# XenoGC.net
KiCad netlist of a schematic drawn in EAGLE
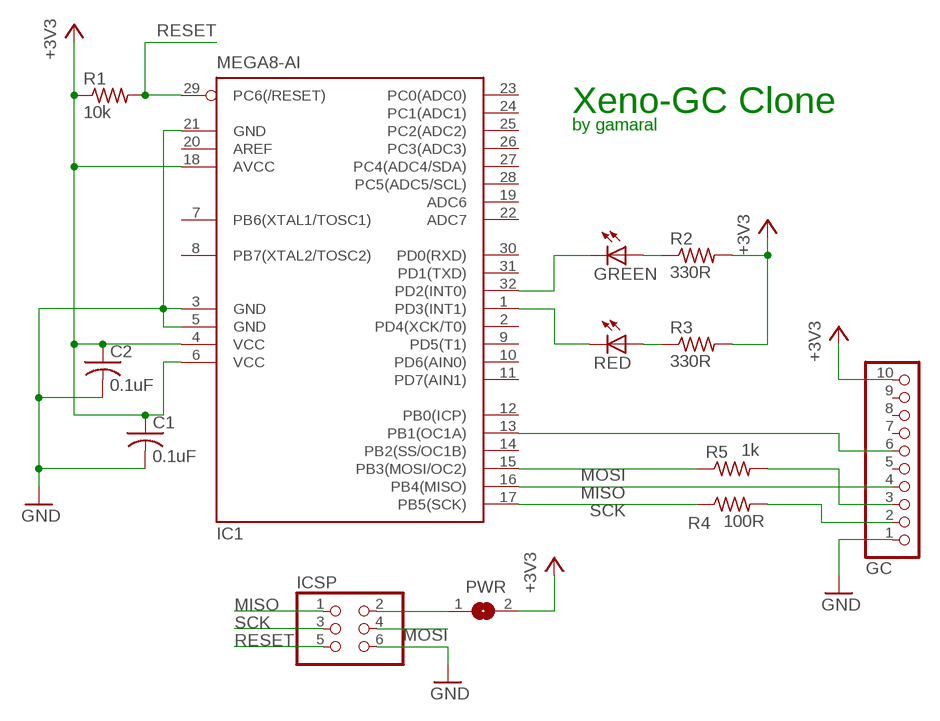
[diagram p0: schematic, sheet 1]

(export (version "E")
  (design (tool "Eeschema 10.0.6"))
  (components
    (comp (ref "C1")
      (value "0.1uF")
      (footprint "eagle-import:C0805K")
      (libsource (lib "eagle-import") (part "C-USC0805K"))
    )
    (comp (ref "C2")
      (value "0.1uF")
      (footprint "eagle-import:C0805K")
      (libsource (lib "eagle-import") (part "C-USC0805K"))
    )
    (comp (ref "GC")
      (value "PINHD-1X10")
      (footprint "eagle-import:1X10")
      (libsource (lib "eagle-import") (part "PINHD-1X10"))
    )
    (comp (ref "GREEN")
      (value "LEDSML1206")
      (footprint "eagle-import:SML1206")
      (libsource (lib "eagle-import") (part "LEDSML1206"))
    )
    (comp (ref "IC1")
      (value "MEGA8-AI")
      (footprint "eagle-import:TQFP32-08")
      (fields (field (name "MPN") "ATMEGA8-16AU"))
      (libsource (lib "eagle-import") (part "MEGA8-AI"))
    )
    (comp (ref "ICSP")
      (value "PINHD-2X3")
      (footprint "eagle-import:2X03")
      (libsource (lib "eagle-import") (part "PINHD-2X3"))
    )
    (comp (ref "PWR") (value "SJ") (footprint "eagle-import:SJ") (libsource (lib "eagle-import") (part "SJ")))
    (comp (ref "R1")
      (value "10k")
      (footprint "eagle-import:R0805W")
      (libsource (lib "eagle-import") (part "R-US_R0805W"))
    )
    (comp (ref "R2")
      (value "330R")
      (footprint "eagle-import:R0805W")
      (libsource (lib "eagle-import") (part "R-US_R0805W"))
    )
    (comp (ref "R3")
      (value "330R")
      (footprint "eagle-import:R0805W")
      (libsource (lib "eagle-import") (part "R-US_R0805W"))
    )
    (comp (ref "R4")
      (value "100R")
      (footprint "eagle-import:R0805W")
      (libsource (lib "eagle-import") (part "R-US_R0805W"))
    )
    (comp (ref "R5")
      (value "1k")
      (footprint "eagle-import:R0805W")
      (libsource (lib "eagle-import") (part "R-US_R0805W"))
    )
    (comp (ref "RED")
      (value "LEDSML1206")
      (footprint "eagle-import:SML1206")
      (libsource (lib "eagle-import") (part "LEDSML1206"))
    )
  )
  (nets
    (net (code "1") (name "+3V3") (class "Default")
      (node (ref "C1") (pin "1") (pinfunction "1_1") (pintype "passive"))
      (node (ref "C2") (pin "1") (pinfunction "1_1") (pintype "passive"))
      (node (ref "GC") (pin "10") (pinfunction "10_10") (pintype "passive"))
      (node (ref "IC1") (pin "18") (pinfunction "AVCC_18") (pintype "power_in"))
      (node (ref "IC1") (pin "4") (pinfunction "VCC_4") (pintype "power_in"))
      (node (ref "IC1") (pin "6") (pinfunction "VCC_6") (pintype "power_in"))
      (node (ref "PWR") (pin "2") (pinfunction "2_2") (pintype "passive"))
      (node (ref "R1") (pin "1") (pinfunction "1_1") (pintype "passive"))
      (node (ref "R2") (pin "2") (pinfunction "2_2") (pintype "passive"))
      (node (ref "R3") (pin "2") (pinfunction "2_2") (pintype "passive"))
    )
    (net (code "2") (name "/MISO") (class "Default")
      (node (ref "GC") (pin "4") (pinfunction "4_4") (pintype "passive"))
      (node (ref "IC1") (pin "16") (pinfunction "PB4(MISO)_16") (pintype "bidirectional"))
      (node (ref "ICSP") (pin "1") (pinfunction "1_1") (pintype "passive"))
    )
    (net (code "3") (name "/MOSI") (class "Default")
      (node (ref "IC1") (pin "15") (pinfunction "PB3(MOSI/OC2)_15") (pintype "bidirectional"))
      (node (ref "ICSP") (pin "4") (pinfunction "4_4") (pintype "passive"))
      (node (ref "R5") (pin "1") (pinfunction "1_1") (pintype "passive"))
    )
    (net (code "4") (name "/RESET") (class "Default")
      (node (ref "IC1") (pin "29") (pinfunction "PC6(/RESET)_29") (pintype "bidirectional"))
      (node (ref "ICSP") (pin "5") (pinfunction "5_5") (pintype "passive"))
      (node (ref "R1") (pin "2") (pinfunction "2_2") (pintype "passive"))
    )
    (net (code "5") (name "/SCK") (class "Default")
      (node (ref "IC1") (pin "17") (pinfunction "PB5(SCK)_17") (pintype "bidirectional"))
      (node (ref "ICSP") (pin "3") (pinfunction "3_3") (pintype "passive"))
      (node (ref "R4") (pin "1") (pinfunction "1_1") (pintype "passive"))
    )
    (net (code "6") (name "GND") (class "Default")
      (node (ref "C1") (pin "2") (pinfunction "2_2") (pintype "passive"))
      (node (ref "C2") (pin "2") (pinfunction "2_2") (pintype "passive"))
      (node (ref "GC") (pin "1") (pinfunction "1_1") (pintype "passive"))
      (node (ref "IC1") (pin "21") (pinfunction "GND_21") (pintype "power_in"))
      (node (ref "IC1") (pin "3") (pinfunction "GND_3") (pintype "power_in"))
      (node (ref "IC1") (pin "5") (pinfunction "GND_5") (pintype "power_in"))
      (node (ref "ICSP") (pin "6") (pinfunction "6_6") (pintype "passive"))
    )
    (net (code "7") (name "Net-(GC-Pad2)") (class "Default")
      (node (ref "GC") (pin "2") (pinfunction "2_2") (pintype "passive"))
      (node (ref "R4") (pin "2") (pinfunction "2_2") (pintype "passive"))
    )
    (net (code "8") (name "Net-(GC-Pad3)") (class "Default")
      (node (ref "GC") (pin "3") (pinfunction "3_3") (pintype "passive"))
      (node (ref "R5") (pin "2") (pinfunction "2_2") (pintype "passive"))
    )
    (net (code "9") (name "Net-(GREEN-PadA)") (class "Default")
      (node (ref "GREEN") (pin "A") (pinfunction "A_A") (pintype "passive"))
      (node (ref "R2") (pin "1") (pinfunction "1_1") (pintype "passive"))
    )
    (net (code "10") (name "Net-(IC1-PB1(OC1A))") (class "Default")
      (node (ref "GC") (pin "6") (pinfunction "6_6") (pintype "passive"))
      (node (ref "IC1") (pin "13") (pinfunction "PB1(OC1A)_13") (pintype "bidirectional"))
    )
    (net (code "11") (name "Net-(IC1-PD2(INT0))") (class "Default")
      (node (ref "GREEN") (pin "C") (pinfunction "C_C") (pintype "passive"))
      (node (ref "IC1") (pin "32") (pinfunction "PD2(INT0)_32") (pintype "bidirectional"))
    )
    (net (code "12") (name "Net-(IC1-PD3(INT1))") (class "Default")
      (node (ref "IC1") (pin "1") (pinfunction "PD3(INT1)_1") (pintype "bidirectional"))
      (node (ref "RED") (pin "C") (pinfunction "C_C") (pintype "passive"))
    )
    (net (code "13") (name "Net-(ICSP-Pad2)") (class "Default")
      (node (ref "ICSP") (pin "2") (pinfunction "2_2") (pintype "passive"))
      (node (ref "PWR") (pin "1") (pinfunction "1_1") (pintype "passive"))
    )
    (net (code "14") (name "Net-(R3-Pad1)") (class "Default")
      (node (ref "R3") (pin "1") (pinfunction "1_1") (pintype "passive"))
      (node (ref "RED") (pin "A") (pinfunction "A_A") (pintype "passive"))
    )
    (net (code "15") (name "unconnected-(GC-Pad5)") (class "Default")
      (node (ref "GC") (pin "5") (pinfunction "5_5") (pintype "passive"))
    )
    (net (code "16") (name "unconnected-(GC-Pad7)") (class "Default")
      (node (ref "GC") (pin "7") (pinfunction "7_7") (pintype "passive"))
    )
    (net (code "17") (name "unconnected-(GC-Pad8)") (class "Default")
      (node (ref "GC") (pin "8") (pinfunction "8_8") (pintype "passive"))
    )
    (net (code "18") (name "unconnected-(GC-Pad9)") (class "Default")
      (node (ref "GC") (pin "9") (pinfunction "9_9") (pintype "passive"))
    )
    (net (code "19") (name "unconnected-(IC1-ADC6-Pad19)") (class "Default")
      (node (ref "IC1") (pin "19") (pinfunction "ADC6_19") (pintype "bidirectional"))
    )
    (net (code "20") (name "unconnected-(IC1-ADC7-Pad22)") (class "Default")
      (node (ref "IC1") (pin "22") (pinfunction "ADC7_22") (pintype "bidirectional"))
    )
    (net (code "21") (name "unconnected-(IC1-AREF-Pad20)") (class "Default")
      (node (ref "IC1") (pin "20") (pinfunction "AREF_20") (pintype "passive"))
    )
    (net (code "22") (name "unconnected-(IC1-PB0(ICP)-Pad12)") (class "Default")
      (node (ref "IC1") (pin "12") (pinfunction "PB0(ICP)_12") (pintype "bidirectional"))
    )
    (net (code "23") (name "unconnected-(IC1-PB2(SS{slash}OC1B)-Pad14)") (class "Default")
      (node (ref "IC1") (pin "14") (pinfunction "PB2(SS/OC1B)_14") (pintype "bidirectional"))
    )
    (net (code "24") (name "unconnected-(IC1-PB6(XTAL1{slash}TOSC1)-Pad7)") (class "Default")
      (node (ref "IC1") (pin "7") (pinfunction "PB6(XTAL1/TOSC1)_7") (pintype "bidirectional"))
    )
    (net (code "25") (name "unconnected-(IC1-PB7(XTAL2{slash}TOSC2)-Pad8)") (class "Default")
      (node (ref "IC1") (pin "8") (pinfunction "PB7(XTAL2/TOSC2)_8") (pintype "bidirectional"))
    )
    (net (code "26") (name "unconnected-(IC1-PC0(ADC0)-Pad23)") (class "Default")
      (node (ref "IC1") (pin "23") (pinfunction "PC0(ADC0)_23") (pintype "bidirectional"))
    )
    (net (code "27") (name "unconnected-(IC1-PC1(ADC1)-Pad24)") (class "Default")
      (node (ref "IC1") (pin "24") (pinfunction "PC1(ADC1)_24") (pintype "bidirectional"))
    )
    (net (code "28") (name "unconnected-(IC1-PC2(ADC2)-Pad25)") (class "Default")
      (node (ref "IC1") (pin "25") (pinfunction "PC2(ADC2)_25") (pintype "bidirectional"))
    )
    (net (code "29") (name "unconnected-(IC1-PC3(ADC3)-Pad26)") (class "Default")
      (node (ref "IC1") (pin "26") (pinfunction "PC3(ADC3)_26") (pintype "bidirectional"))
    )
    (net (code "30") (name "unconnected-(IC1-PC4(ADC4{slash}SDA)-Pad27)") (class "Default")
      (node (ref "IC1") (pin "27") (pinfunction "PC4(ADC4/SDA)_27") (pintype "bidirectional"))
    )
    (net (code "31") (name "unconnected-(IC1-PC5(ADC5{slash}SCL)-Pad28)") (class "Default")
      (node (ref "IC1") (pin "28") (pinfunction "PC5(ADC5/SCL)_28") (pintype "bidirectional"))
    )
    (net (code "32") (name "unconnected-(IC1-PD0(RXD)-Pad30)") (class "Default")
      (node (ref "IC1") (pin "30") (pinfunction "PD0(RXD)_30") (pintype "bidirectional"))
    )
    (net (code "33") (name "unconnected-(IC1-PD1(TXD)-Pad31)") (class "Default")
      (node (ref "IC1") (pin "31") (pinfunction "PD1(TXD)_31") (pintype "bidirectional"))
    )
    (net (code "34") (name "unconnected-(IC1-PD4(XCK{slash}T0)-Pad2)") (class "Default")
      (node (ref "IC1") (pin "2") (pinfunction "PD4(XCK/T0)_2") (pintype "bidirectional"))
    )
    (net (code "35") (name "unconnected-(IC1-PD5(T1)-Pad9)") (class "Default")
      (node (ref "IC1") (pin "9") (pinfunction "PD5(T1)_9") (pintype "bidirectional"))
    )
    (net (code "36") (name "unconnected-(IC1-PD6(AIN0)-Pad10)") (class "Default")
      (node (ref "IC1") (pin "10") (pinfunction "PD6(AIN0)_10") (pintype "bidirectional"))
    )
    (net (code "37") (name "unconnected-(IC1-PD7(AIN1)-Pad11)") (class "Default")
      (node (ref "IC1") (pin "11") (pinfunction "PD7(AIN1)_11") (pintype "bidirectional"))
    )
  )
)
